# arduino-shield.net
KiCad netlist of a schematic drawn in EAGLE
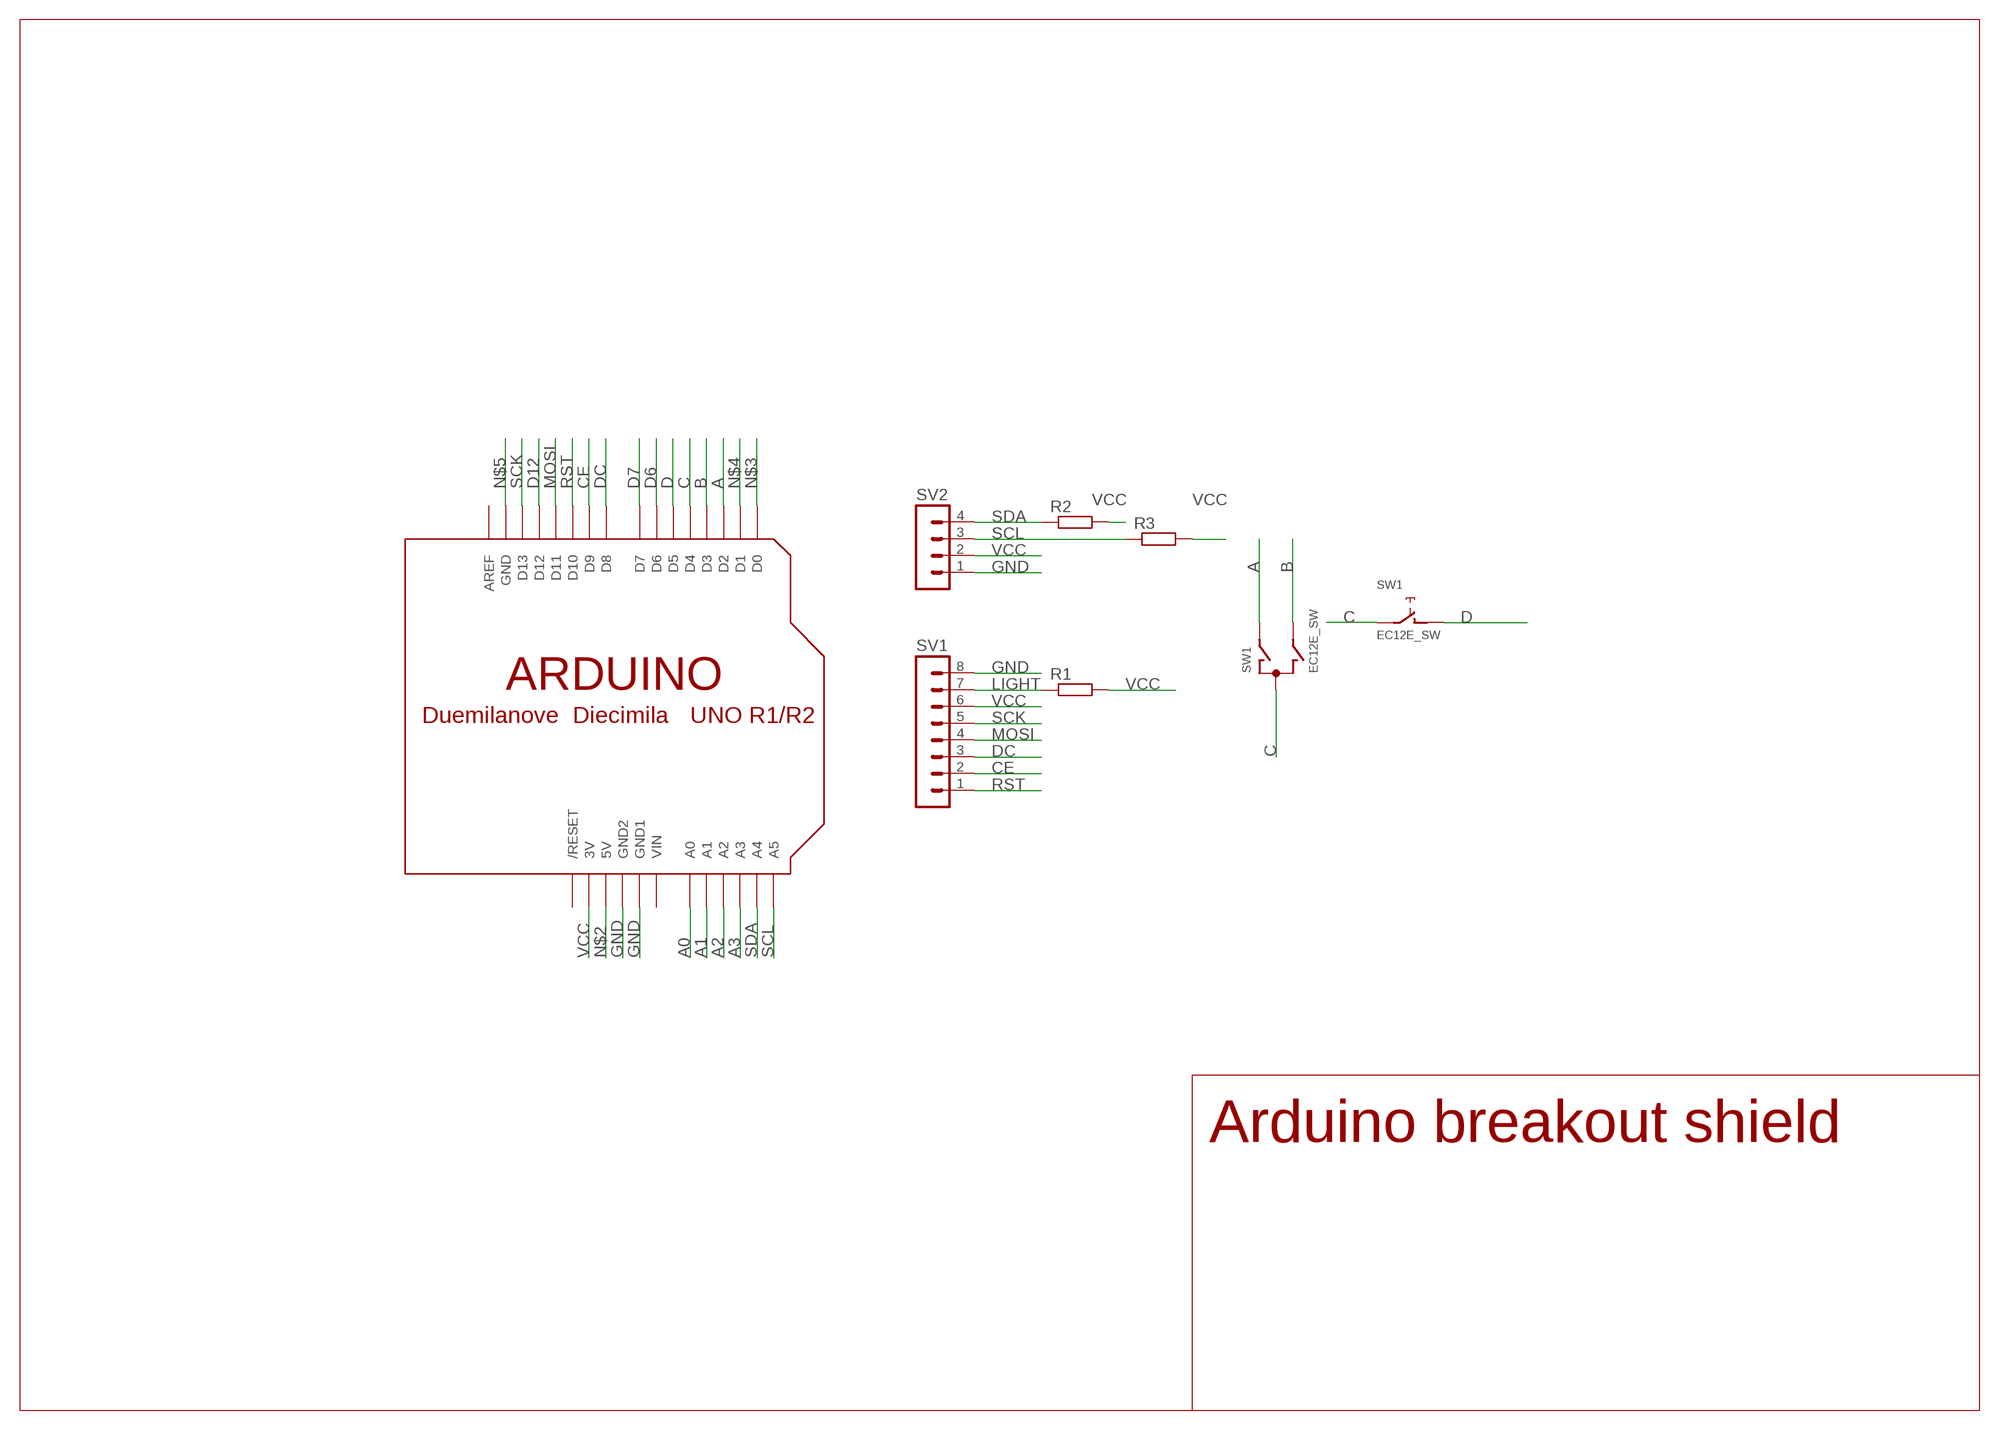
[diagram p0: schematic, sheet 1]
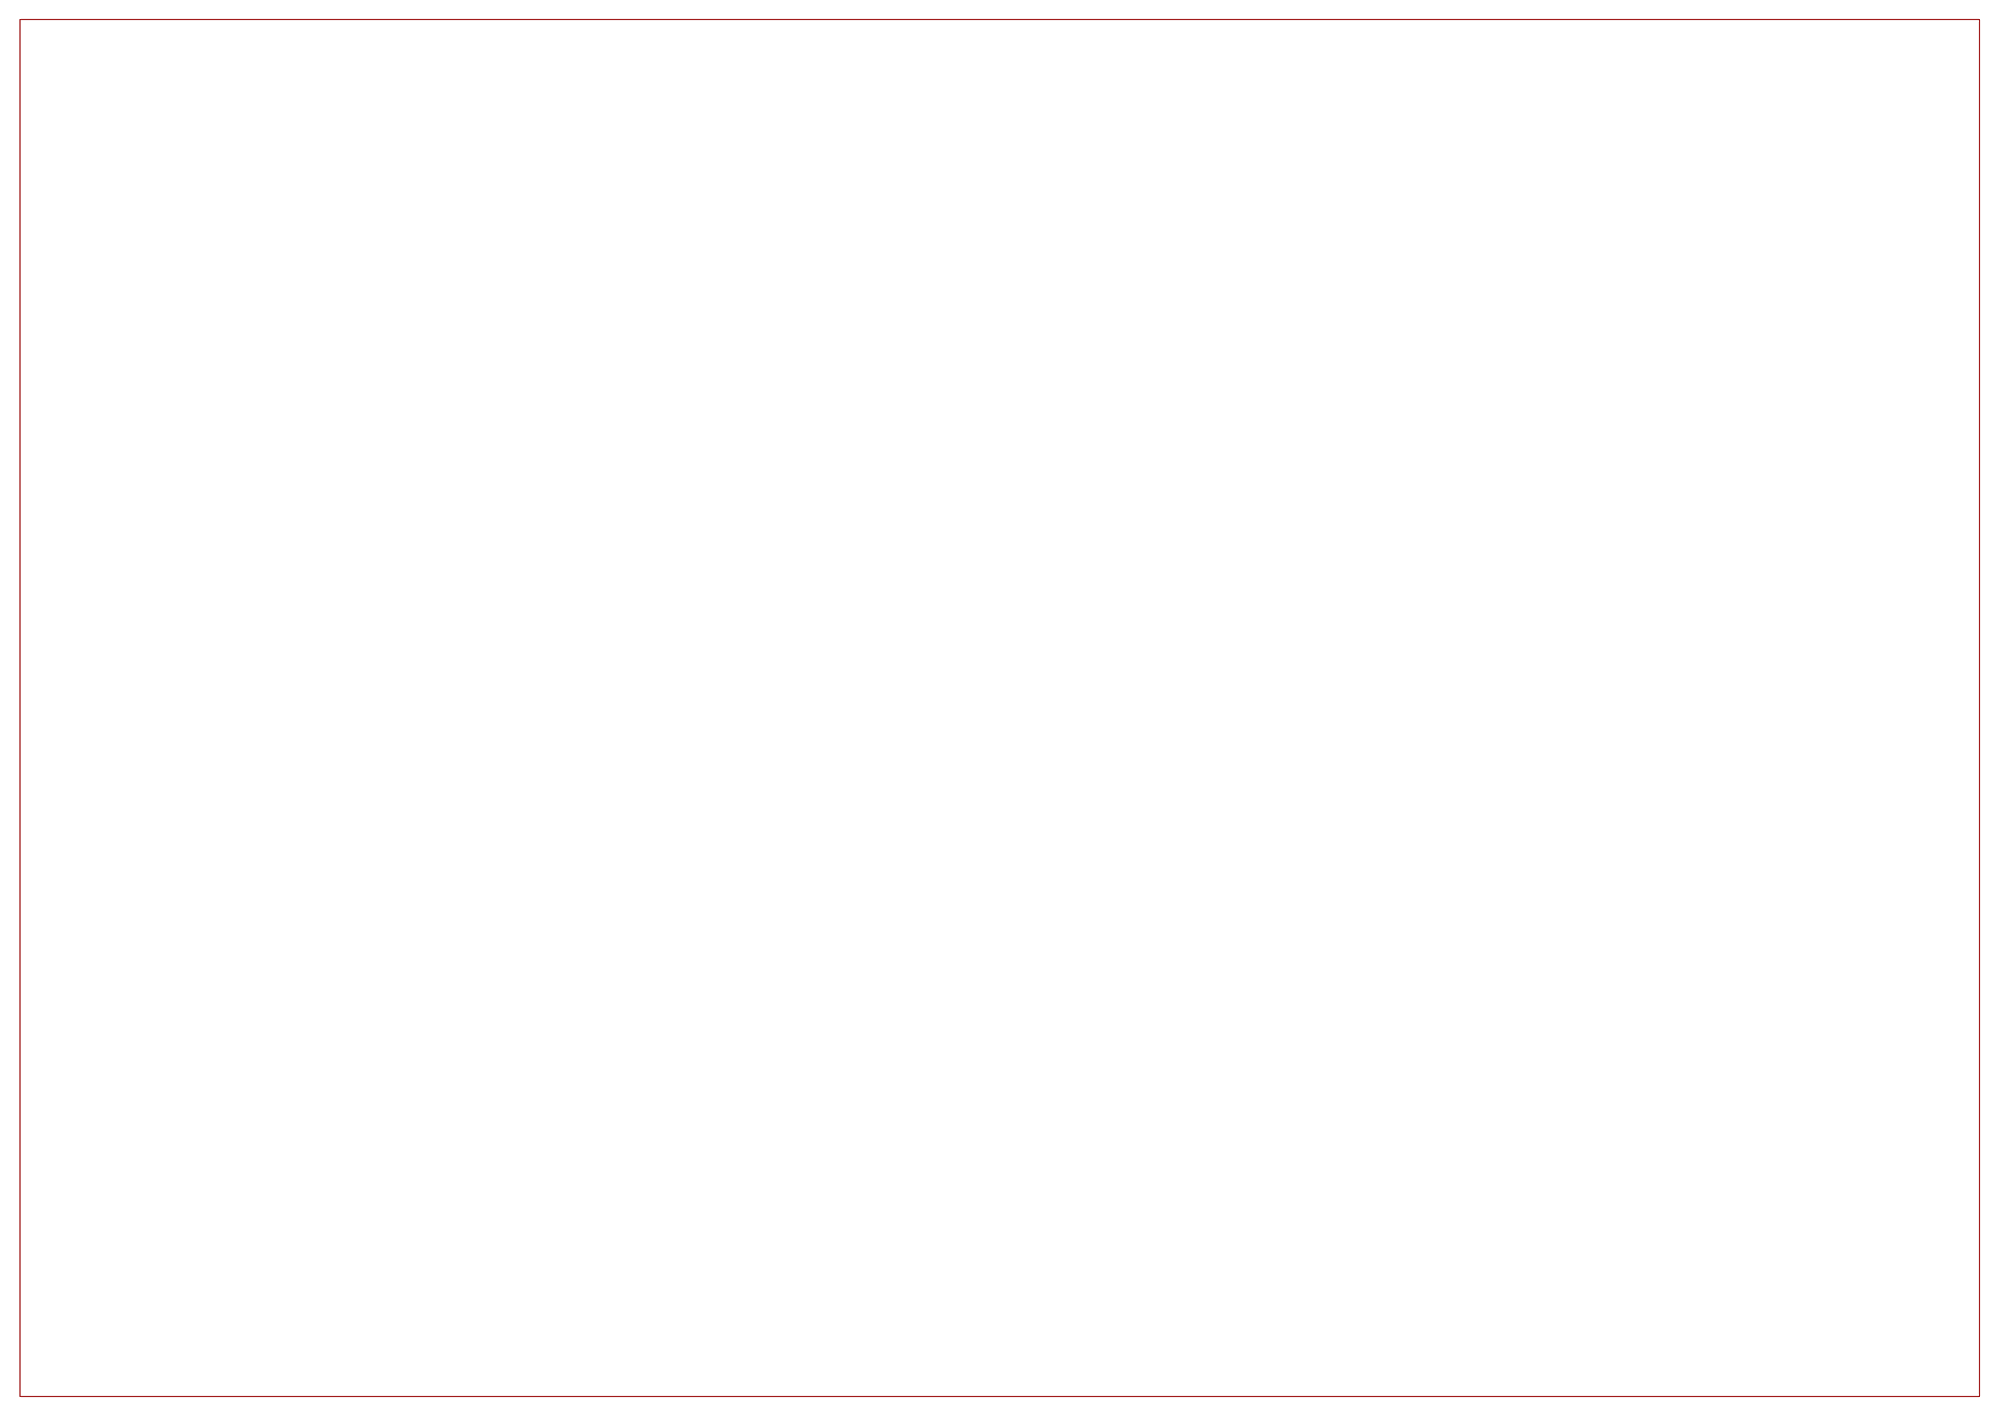
[diagram p1: schematic, sheet 2]

(export (version "E")
  (design (tool "Eeschema 10.0.6"))
  (components
    (comp (ref "R1")
      (value "R-EU_R0805")
      (footprint "eagle-import:R0805")
      (libsource (lib "eagle-import") (part "R-EU_R0805"))
    )
    (comp (ref "R2")
      (value "R-EU_R0805")
      (footprint "eagle-import:R0805")
      (libsource (lib "eagle-import") (part "R-EU_R0805"))
    )
    (comp (ref "R3")
      (value "R-EU_R0805")
      (footprint "eagle-import:R0805")
      (libsource (lib "eagle-import") (part "R-EU_R0805"))
    )
    (comp (ref "SV1")
      (value "MA08-1")
      (footprint "eagle-import:MA08-1")
      (libsource (lib "eagle-import") (part "MA08-1"))
    )
    (comp (ref "SV2")
      (value "MA04-1")
      (footprint "eagle-import:MA04-1")
      (libsource (lib "eagle-import") (part "MA04-1"))
    )
    (comp (ref "SW1")
      (value "EC12E_SW")
      (footprint "eagle-import:ALPS_EC12E_SW")
      (fields (field (name "MPN") "EC12E2424407"))
      (libsource (lib "eagle-import") (part "EC12E_SW"))
    )
    (comp (ref "U$1")
      (value "ARDUINO-NOHOLE")
      (footprint "eagle-import:ARDUINO-NOHOLE")
      (libsource (lib "eagle-import") (part "ARDUINO-NOHOLE"))
    )
  )
  (nets
    (net (code "1") (name "A") (class "Default")
      (node (ref "SW1") (pin "A") (pinfunction "A_A") (pintype "passive"))
      (node (ref "U$1") (pin "D2") (pinfunction "D2_D2") (pintype "bidirectional"))
    )
    (net (code "2") (name "A0") (class "Default")
      (node (ref "U$1") (pin "A0") (pinfunction "A0_A0") (pintype "bidirectional"))
    )
    (net (code "3") (name "A1") (class "Default")
      (node (ref "U$1") (pin "A1") (pinfunction "A1_A1") (pintype "bidirectional"))
    )
    (net (code "4") (name "A2") (class "Default")
      (node (ref "U$1") (pin "A2") (pinfunction "A2_A2") (pintype "bidirectional"))
    )
    (net (code "5") (name "A3") (class "Default")
      (node (ref "U$1") (pin "A3") (pinfunction "A3_A3") (pintype "bidirectional"))
    )
    (net (code "6") (name "B") (class "Default")
      (node (ref "SW1") (pin "B") (pinfunction "B_B") (pintype "passive"))
      (node (ref "U$1") (pin "D3") (pinfunction "D3_D3") (pintype "bidirectional"))
    )
    (net (code "7") (name "C") (class "Default")
      (node (ref "SW1") (pin "C") (pinfunction "C_C") (pintype "passive"))
      (node (ref "SW1") (pin "E") (pinfunction "2_E") (pintype "passive"))
      (node (ref "U$1") (pin "D4") (pinfunction "D4_D4") (pintype "bidirectional"))
    )
    (net (code "8") (name "CE") (class "Default")
      (node (ref "SV1") (pin "2") (pinfunction "2_2") (pintype "passive"))
      (node (ref "U$1") (pin "D9") (pinfunction "D9_D9") (pintype "bidirectional"))
    )
    (net (code "9") (name "D") (class "Default")
      (node (ref "SW1") (pin "D") (pinfunction "1_D") (pintype "passive"))
      (node (ref "U$1") (pin "D5") (pinfunction "D5_D5") (pintype "bidirectional"))
    )
    (net (code "10") (name "D6") (class "Default")
      (node (ref "U$1") (pin "D6") (pinfunction "D6_D6") (pintype "bidirectional"))
    )
    (net (code "11") (name "D7") (class "Default")
      (node (ref "U$1") (pin "D7") (pinfunction "D7_D7") (pintype "bidirectional"))
    )
    (net (code "12") (name "D12") (class "Default")
      (node (ref "U$1") (pin "D12") (pinfunction "D12_D12") (pintype "bidirectional"))
    )
    (net (code "13") (name "DC") (class "Default")
      (node (ref "SV1") (pin "3") (pinfunction "3_3") (pintype "passive"))
      (node (ref "U$1") (pin "D8") (pinfunction "D8_D8") (pintype "bidirectional"))
    )
    (net (code "14") (name "GND") (class "Default")
      (node (ref "SV1") (pin "8") (pinfunction "8_8") (pintype "passive"))
      (node (ref "SV2") (pin "1") (pinfunction "1_1") (pintype "passive"))
      (node (ref "U$1") (pin "GND1") (pinfunction "GND1_GND1") (pintype "power_in"))
      (node (ref "U$1") (pin "GND2") (pinfunction "GND2_GND2") (pintype "power_in"))
    )
    (net (code "15") (name "LIGHT") (class "Default")
      (node (ref "R1") (pin "1") (pinfunction "1_1") (pintype "passive"))
      (node (ref "SV1") (pin "7") (pinfunction "7_7") (pintype "passive"))
    )
    (net (code "16") (name "MOSI") (class "Default")
      (node (ref "SV1") (pin "4") (pinfunction "4_4") (pintype "passive"))
      (node (ref "U$1") (pin "D11") (pinfunction "D11_D11") (pintype "bidirectional"))
    )
    (net (code "17") (name "N$2") (class "Default")
      (node (ref "U$1") (pin "5V") (pinfunction "5V_5V") (pintype "power_in"))
    )
    (net (code "18") (name "N$3") (class "Default")
      (node (ref "U$1") (pin "D0") (pinfunction "D0_D0") (pintype "bidirectional"))
    )
    (net (code "19") (name "N$4") (class "Default")
      (node (ref "U$1") (pin "D1") (pinfunction "D1_D1") (pintype "bidirectional"))
    )
    (net (code "20") (name "N$5") (class "Default")
      (node (ref "U$1") (pin "GND") (pinfunction "GND_GND") (pintype "power_in"))
    )
    (net (code "21") (name "RST") (class "Default")
      (node (ref "SV1") (pin "1") (pinfunction "1_1") (pintype "passive"))
      (node (ref "U$1") (pin "D10") (pinfunction "D10_D10") (pintype "bidirectional"))
    )
    (net (code "22") (name "SCK") (class "Default")
      (node (ref "SV1") (pin "5") (pinfunction "5_5") (pintype "passive"))
      (node (ref "U$1") (pin "D13") (pinfunction "D13_D13") (pintype "bidirectional"))
    )
    (net (code "23") (name "SCL") (class "Default")
      (node (ref "R3") (pin "1") (pinfunction "1_1") (pintype "passive"))
      (node (ref "SV2") (pin "3") (pinfunction "3_3") (pintype "passive"))
      (node (ref "U$1") (pin "A5") (pinfunction "A5_A5") (pintype "bidirectional"))
    )
    (net (code "24") (name "SDA") (class "Default")
      (node (ref "R2") (pin "1") (pinfunction "1_1") (pintype "passive"))
      (node (ref "SV2") (pin "4") (pinfunction "4_4") (pintype "passive"))
      (node (ref "U$1") (pin "A4") (pinfunction "A4_A4") (pintype "bidirectional"))
    )
    (net (code "25") (name "VCC") (class "Default")
      (node (ref "R1") (pin "2") (pinfunction "2_2") (pintype "passive"))
      (node (ref "R2") (pin "2") (pinfunction "2_2") (pintype "passive"))
      (node (ref "R3") (pin "2") (pinfunction "2_2") (pintype "passive"))
      (node (ref "SV1") (pin "6") (pinfunction "6_6") (pintype "passive"))
      (node (ref "SV2") (pin "2") (pinfunction "2_2") (pintype "passive"))
      (node (ref "U$1") (pin "3V") (pinfunction "3V_3V") (pintype "power_in"))
    )
    (net (code "26") (name "VIN") (class "Default")
      (node (ref "U$1") (pin "VIN") (pinfunction "VIN_VIN") (pintype "power_in"))
    )
    (net (code "27") (name "unconnected-(U$1-PadAREF)") (class "Default")
      (node (ref "U$1") (pin "AREF") (pinfunction "AREF_AREF") (pintype "bidirectional"))
    )
    (net (code "28") (name "unconnected-(U$1-{slash}RESET-PadRESET)") (class "Default")
      (node (ref "U$1") (pin "RESET") (pinfunction "/RESET_RESET") (pintype "bidirectional"))
    )
  )
)
